# ST-Link-V2_1.net
KiCad netlist of a schematic drawn in Altium Designer
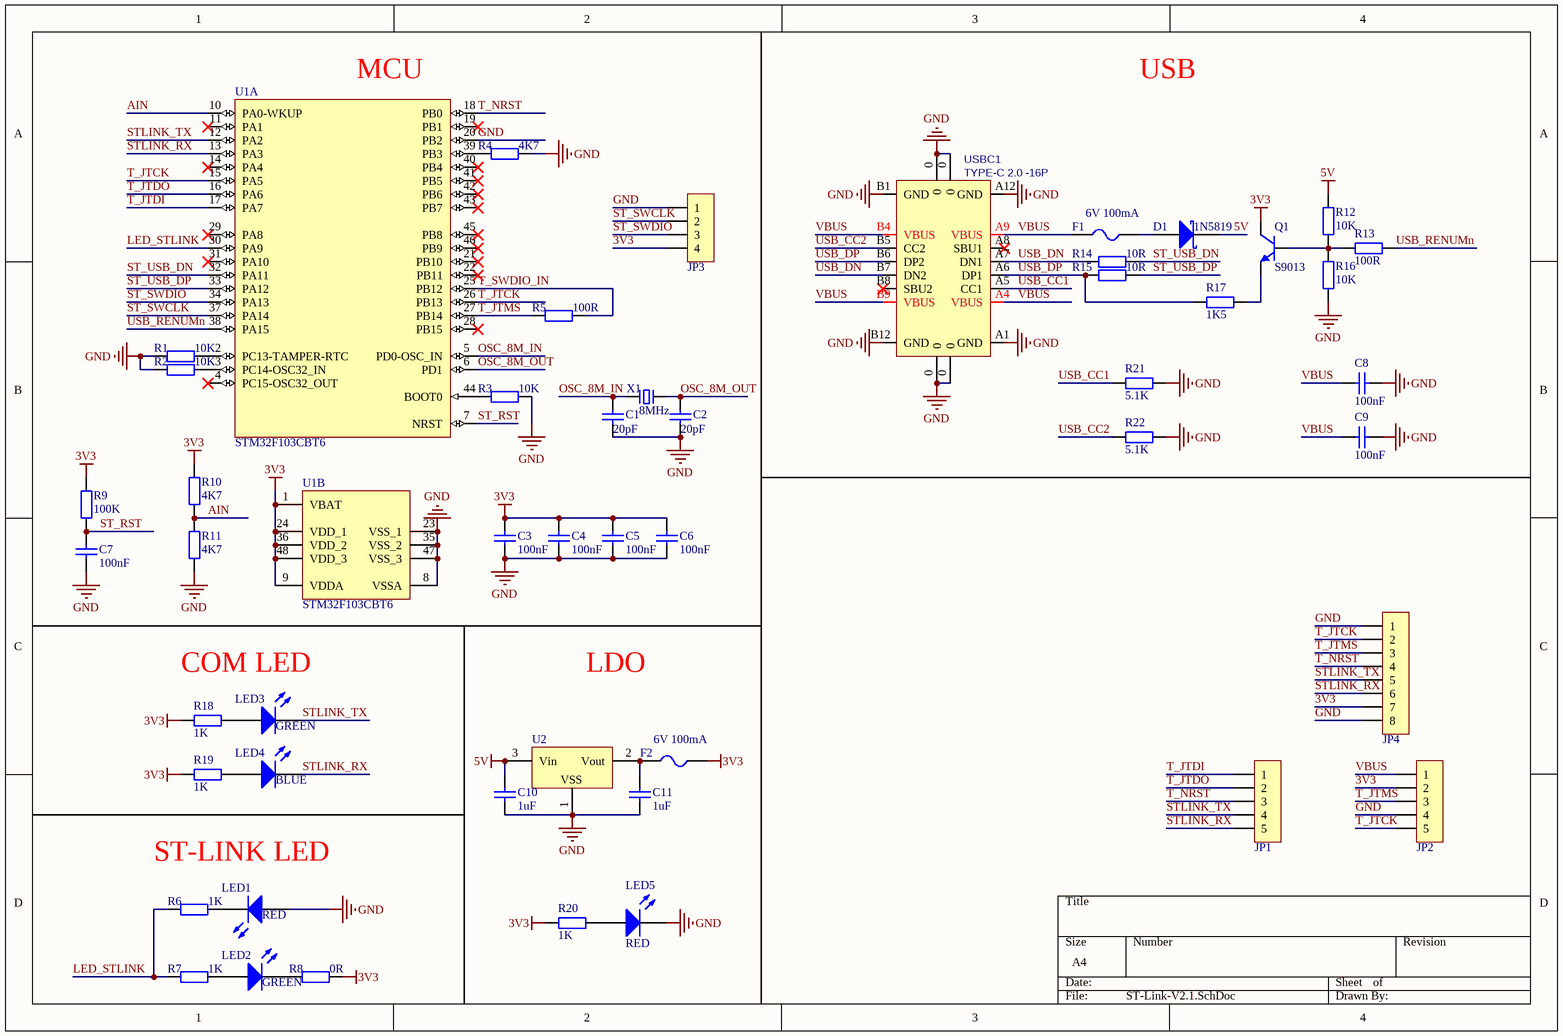
[diagram p0: ST-Link-V2.1.SchDoc]

(export (version "E")
  (design (tool "Eeschema 10.0.6"))
  (components
    (comp (ref "C1")
      (value "20pF")
      (footprint "C0402_M")
      (description "贴片电容/MLCC电容")
      (libsource (lib "0.1 - 电阻-电容-电感-保险丝-晶振-晶体-磁珠-电位器-法拉电容-馈通电容") (part "C"))
    )
    (comp (ref "C2")
      (value "20pF")
      (footprint "C0402_M")
      (description "贴片电容/MLCC电容")
      (libsource (lib "0.1 - 电阻-电容-电感-保险丝-晶振-晶体-磁珠-电位器-法拉电容-馈通电容") (part "C"))
    )
    (comp (ref "C3")
      (value "100nF")
      (footprint "C0402_M")
      (description "贴片电容/MLCC电容")
      (libsource (lib "0.1 - 电阻-电容-电感-保险丝-晶振-晶体-磁珠-电位器-法拉电容-馈通电容") (part "C"))
    )
    (comp (ref "C4")
      (value "100nF")
      (footprint "C0402_M")
      (description "贴片电容/MLCC电容")
      (libsource (lib "0.1 - 电阻-电容-电感-保险丝-晶振-晶体-磁珠-电位器-法拉电容-馈通电容") (part "C"))
    )
    (comp (ref "C5")
      (value "100nF")
      (footprint "C0402_M")
      (description "贴片电容/MLCC电容")
      (libsource (lib "0.1 - 电阻-电容-电感-保险丝-晶振-晶体-磁珠-电位器-法拉电容-馈通电容") (part "C"))
    )
    (comp (ref "C6")
      (value "100nF")
      (footprint "C0402_M")
      (description "贴片电容/MLCC电容")
      (libsource (lib "0.1 - 电阻-电容-电感-保险丝-晶振-晶体-磁珠-电位器-法拉电容-馈通电容") (part "C"))
    )
    (comp (ref "C7")
      (value "100nF")
      (footprint "C0402_M")
      (description "贴片电容/MLCC电容")
      (libsource (lib "0.1 - 电阻-电容-电感-保险丝-晶振-晶体-磁珠-电位器-法拉电容-馈通电容") (part "C"))
    )
    (comp (ref "C8")
      (value "100nF")
      (footprint "C0402_M")
      (description "贴片电容/MLCC电容")
      (libsource (lib "0.1 - 电阻-电容-电感-保险丝-晶振-晶体-磁珠-电位器-法拉电容-馈通电容") (part "C"))
    )
    (comp (ref "C9")
      (value "100nF")
      (footprint "C0402_M")
      (description "贴片电容/MLCC电容")
      (libsource (lib "0.1 - 电阻-电容-电感-保险丝-晶振-晶体-磁珠-电位器-法拉电容-馈通电容") (part "C"))
    )
    (comp (ref "C10")
      (value "1uF")
      (footprint "C0402_M")
      (description "贴片电容/MLCC电容")
      (libsource (lib "0.1 - 电阻-电容-电感-保险丝-晶振-晶体-磁珠-电位器-法拉电容-馈通电容") (part "C"))
    )
    (comp (ref "C11")
      (value "1uF")
      (footprint "C0402_M")
      (description "贴片电容/MLCC电容")
      (libsource (lib "0.1 - 电阻-电容-电感-保险丝-晶振-晶体-磁珠-电位器-法拉电容-馈通电容") (part "C"))
    )
    (comp (ref "D1")
      (value "1N5819")
      (footprint "SOD-323")
      (description "肖特基二极管")
      (libsource (lib "0.2 - 二极管-TVS-ESD-整流桥-放电管") (part "1N5819"))
    )
    (comp (ref "F1")
      (value "6V 100mA")
      (footprint "F0805")
      (description "方形保险丝")
      (libsource (lib "0.1 - 电阻-电容-电感-保险丝-晶振-晶体-磁珠-电位器-法拉电容-馈通电容") (part "FUSE-8.5*4.0*8.0"))
    )
    (comp (ref "F2")
      (value "6V 100mA")
      (footprint "F0805")
      (description "方形保险丝")
      (libsource (lib "0.1 - 电阻-电容-电感-保险丝-晶振-晶体-磁珠-电位器-法拉电容-馈通电容") (part "FUSE-8.5*4.0*8.0"))
    )
    (comp (ref "JP1")
      (value "HDR-1X5")
      (footprint "HDR2.54-WS-5P")
      (description "5P接插件")
      (libsource (lib "5.5 - 2.54mm连接器(KF2EDGK_XH2.54_2.54排针排母)") (part "Header 5"))
    )
    (comp (ref "JP2")
      (value "HDR-1X5")
      (footprint "HDR2.54-WS-5P")
      (description "5P接插件")
      (libsource (lib "5.5 - 2.54mm连接器(KF2EDGK_XH2.54_2.54排针排母)") (part "Header 5"))
    )
    (comp (ref "JP3")
      (value "HDR-1X4")
      (footprint "HDR1.27-LI-4P")
      (description "4P接插件")
      (libsource (lib "5.5 - 2.54mm连接器(KF2EDGK_XH2.54_2.54排针排母)") (part "Header 4"))
    )
    (comp (ref "JP4")
      (value "CON-8P")
      (footprint "FPC0.5-WT-8P-双侧触点")
      (description "8P连接器")
      (libsource (lib "4.9 - 0.5mm连接器(FPC0.5)") (part "Header 8"))
    )
    (comp (ref "LED1")
      (value "RED")
      (footprint "LED0402_R")
      (description "贴片LED")
      (libsource (lib "0.3 - LED发光二极管-IR二极管_接收管-光耦") (part "LED"))
    )
    (comp (ref "LED2")
      (value "GREEN")
      (footprint "LED0402_G")
      (description "贴片LED")
      (libsource (lib "0.3 - LED发光二极管-IR二极管_接收管-光耦") (part "LED"))
    )
    (comp (ref "LED3")
      (value "GREEN")
      (footprint "LED0402_G")
      (description "贴片LED")
      (libsource (lib "0.3 - LED发光二极管-IR二极管_接收管-光耦") (part "LED"))
    )
    (comp (ref "LED4")
      (value "BLUE")
      (footprint "LED0402_B")
      (description "贴片LED")
      (libsource (lib "0.3 - LED发光二极管-IR二极管_接收管-光耦") (part "LED"))
    )
    (comp (ref "LED5")
      (value "RED")
      (footprint "LED0402_R")
      (description "贴片LED")
      (libsource (lib "0.3 - LED发光二极管-IR二极管_接收管-光耦") (part "LED"))
    )
    (comp (ref "Q1")
      (value "S9013")
      (footprint "SOT23-3M")
      (description "低频放大-NPN型")
      (libsource (lib "0.4 - 三极管-场效应管-可控硅") (part "9013-DIP"))
    )
    (comp (ref "R1")
      (value "10K")
      (footprint "R0402_M")
      (description "贴片电阻")
      (libsource (lib "0.1 - 电阻-电容-电感-保险丝-晶振-晶体-磁珠-电位器-法拉电容-馈通电容") (part "R"))
    )
    (comp (ref "R2")
      (value "10K")
      (footprint "R0402_M")
      (description "贴片电阻")
      (libsource (lib "0.1 - 电阻-电容-电感-保险丝-晶振-晶体-磁珠-电位器-法拉电容-馈通电容") (part "R"))
    )
    (comp (ref "R3")
      (value "10K")
      (footprint "R0402_M")
      (description "贴片电阻")
      (libsource (lib "0.1 - 电阻-电容-电感-保险丝-晶振-晶体-磁珠-电位器-法拉电容-馈通电容") (part "R"))
    )
    (comp (ref "R4")
      (value "4K7")
      (footprint "R0402_M")
      (description "贴片电阻")
      (libsource (lib "0.1 - 电阻-电容-电感-保险丝-晶振-晶体-磁珠-电位器-法拉电容-馈通电容") (part "R"))
    )
    (comp (ref "R5")
      (value "100R")
      (footprint "R0402_M")
      (description "贴片电阻")
      (libsource (lib "0.1 - 电阻-电容-电感-保险丝-晶振-晶体-磁珠-电位器-法拉电容-馈通电容") (part "R"))
    )
    (comp (ref "R6")
      (value "1K")
      (footprint "R0402_M")
      (description "贴片电阻")
      (libsource (lib "0.1 - 电阻-电容-电感-保险丝-晶振-晶体-磁珠-电位器-法拉电容-馈通电容") (part "R"))
    )
    (comp (ref "R7")
      (value "1K")
      (footprint "R0402_M")
      (description "贴片电阻")
      (libsource (lib "0.1 - 电阻-电容-电感-保险丝-晶振-晶体-磁珠-电位器-法拉电容-馈通电容") (part "R"))
    )
    (comp (ref "R8")
      (value "0R")
      (footprint "R0402_M")
      (description "贴片电阻")
      (libsource (lib "0.1 - 电阻-电容-电感-保险丝-晶振-晶体-磁珠-电位器-法拉电容-馈通电容") (part "R"))
    )
    (comp (ref "R9")
      (value "100K")
      (footprint "R0402_M")
      (description "贴片电阻")
      (libsource (lib "0.1 - 电阻-电容-电感-保险丝-晶振-晶体-磁珠-电位器-法拉电容-馈通电容") (part "R"))
    )
    (comp (ref "R10")
      (value "4K7")
      (footprint "R0402_M")
      (description "贴片电阻")
      (libsource (lib "0.1 - 电阻-电容-电感-保险丝-晶振-晶体-磁珠-电位器-法拉电容-馈通电容") (part "R"))
    )
    (comp (ref "R11")
      (value "4K7")
      (footprint "R0402_M")
      (description "贴片电阻")
      (libsource (lib "0.1 - 电阻-电容-电感-保险丝-晶振-晶体-磁珠-电位器-法拉电容-馈通电容") (part "R"))
    )
    (comp (ref "R12")
      (value "10K")
      (footprint "R0402_M")
      (description "贴片电阻")
      (libsource (lib "0.1 - 电阻-电容-电感-保险丝-晶振-晶体-磁珠-电位器-法拉电容-馈通电容") (part "R"))
    )
    (comp (ref "R13")
      (value "100R")
      (footprint "R0402_M")
      (description "贴片电阻")
      (libsource (lib "0.1 - 电阻-电容-电感-保险丝-晶振-晶体-磁珠-电位器-法拉电容-馈通电容") (part "R"))
    )
    (comp (ref "R14")
      (value "10R")
      (footprint "R0402_M")
      (description "贴片电阻")
      (libsource (lib "0.1 - 电阻-电容-电感-保险丝-晶振-晶体-磁珠-电位器-法拉电容-馈通电容") (part "R"))
    )
    (comp (ref "R15")
      (value "10R")
      (footprint "R0402_M")
      (description "贴片电阻")
      (libsource (lib "0.1 - 电阻-电容-电感-保险丝-晶振-晶体-磁珠-电位器-法拉电容-馈通电容") (part "R"))
    )
    (comp (ref "R16")
      (value "10K")
      (footprint "R0402_M")
      (description "贴片电阻")
      (libsource (lib "0.1 - 电阻-电容-电感-保险丝-晶振-晶体-磁珠-电位器-法拉电容-馈通电容") (part "R"))
    )
    (comp (ref "R17")
      (value "1K5")
      (footprint "R0402_M")
      (description "贴片电阻")
      (libsource (lib "0.1 - 电阻-电容-电感-保险丝-晶振-晶体-磁珠-电位器-法拉电容-馈通电容") (part "R"))
    )
    (comp (ref "R18")
      (value "1K")
      (footprint "R0402_M")
      (description "贴片电阻")
      (libsource (lib "0.1 - 电阻-电容-电感-保险丝-晶振-晶体-磁珠-电位器-法拉电容-馈通电容") (part "R"))
    )
    (comp (ref "R19")
      (value "1K")
      (footprint "R0402_M")
      (description "贴片电阻")
      (libsource (lib "0.1 - 电阻-电容-电感-保险丝-晶振-晶体-磁珠-电位器-法拉电容-馈通电容") (part "R"))
    )
    (comp (ref "R20")
      (value "1K")
      (footprint "R0402_M")
      (description "贴片电阻")
      (libsource (lib "0.1 - 电阻-电容-电感-保险丝-晶振-晶体-磁珠-电位器-法拉电容-馈通电容") (part "R"))
    )
    (comp (ref "R21")
      (value "5.1K")
      (footprint "R0402_M")
      (description "贴片电阻")
      (libsource (lib "0.1 - 电阻-电容-电感-保险丝-晶振-晶体-磁珠-电位器-法拉电容-馈通电容") (part "R"))
    )
    (comp (ref "R22")
      (value "5.1K")
      (footprint "R0402_M")
      (description "贴片电阻")
      (libsource (lib "0.1 - 电阻-电容-电感-保险丝-晶振-晶体-磁珠-电位器-法拉电容-馈通电容") (part "R"))
    )
    (comp (ref "U1")
      (value "STM32F103CBT6")
      (footprint "STM-LQFP48_N")
      (libsource (lib "2.4 - STM32 F1系列单片机") (part "STM32F103CBT6"))
    )
    (comp (ref "U2")
      (value "XC6206P332MR")
      (footprint "SOT23-3N")
      (description "LDO 3.3V/0.25A")
      (libsource (lib "0.7 - 电源类芯片") (part "XC6206P332MR"))
    )
    (comp (ref "USBC1")
      (value "TYPE-C 2.0 -16P")
      (footprint "USB-C-SMD_16P")
      (description "USB2.0_Type-C_16Pin母座")
      (libsource (lib "0.6 - 电源_音频_USB Type-C_HDMI_XT60_5557_D-SUB_RJ45_SD-TF_SIM插座") (part "USB2.0_Type-C_16Pin"))
    )
    (comp (ref "X1")
      (value "8MHz")
      (footprint "OSC-5032-2P")
      (description "2脚无源晶振(谐振器）")
      (libsource (lib "0.1 - 电阻-电容-电感-保险丝-晶振-晶体-磁珠-电位器-法拉电容-馈通电容") (part "XTAL-2P"))
    )
  )
  (nets
    (net (code "1") (name "/AIN") (class "Default")
      (node (ref "R10") (pin "1") (pinfunction "1_1") (pintype "passive"))
      (node (ref "R11") (pin "2") (pinfunction "2_2") (pintype "passive"))
      (node (ref "U1") (pin "10") (pinfunction "PA0-WKUP_10") (pintype "bidirectional"))
    )
    (net (code "2") (name "/LED_STLINK") (class "Default")
      (node (ref "R6") (pin "1") (pinfunction "1_1") (pintype "passive"))
      (node (ref "R7") (pin "1") (pinfunction "1_1") (pintype "passive"))
      (node (ref "U1") (pin "30") (pinfunction "PA9_30") (pintype "bidirectional"))
    )
    (net (code "3") (name "/OSC_8M_IN") (class "Default")
      (node (ref "C1") (pin "2") (pinfunction "2_2") (pintype "passive"))
      (node (ref "U1") (pin "5") (pinfunction "PD0-OSC_IN_5") (pintype "bidirectional"))
      (node (ref "X1") (pin "1") (pinfunction "1_1") (pintype "passive"))
    )
    (net (code "4") (name "/OSC_8M_OUT") (class "Default")
      (node (ref "C2") (pin "2") (pinfunction "2_2") (pintype "passive"))
      (node (ref "U1") (pin "6") (pinfunction "PD1_6") (pintype "bidirectional"))
      (node (ref "X1") (pin "2") (pinfunction "2_2") (pintype "passive"))
    )
    (net (code "5") (name "/STLINK_RX") (class "Default")
      (node (ref "JP1") (pin "5") (pinfunction "5_5") (pintype "passive"))
      (node (ref "JP4") (pin "6") (pinfunction "6_6") (pintype "passive"))
      (node (ref "LED4") (pin "2") (pinfunction "K_2") (pintype "passive"))
      (node (ref "U1") (pin "13") (pinfunction "PA3_13") (pintype "bidirectional"))
    )
    (net (code "6") (name "/STLINK_TX") (class "Default")
      (node (ref "JP1") (pin "4") (pinfunction "4_4") (pintype "passive"))
      (node (ref "JP4") (pin "5") (pinfunction "5_5") (pintype "passive"))
      (node (ref "LED3") (pin "2") (pinfunction "K_2") (pintype "passive"))
      (node (ref "U1") (pin "12") (pinfunction "PA2_12") (pintype "bidirectional"))
    )
    (net (code "7") (name "/ST_RST") (class "Default")
      (node (ref "C7") (pin "2") (pinfunction "2_2") (pintype "passive"))
      (node (ref "R9") (pin "1") (pinfunction "1_1") (pintype "passive"))
      (node (ref "U1") (pin "7") (pinfunction "NRST_7") (pintype "bidirectional"))
    )
    (net (code "8") (name "/ST_SWCLK") (class "Default")
      (node (ref "JP3") (pin "2") (pinfunction "2_2") (pintype "passive"))
      (node (ref "U1") (pin "37") (pinfunction "PA14_37") (pintype "bidirectional"))
    )
    (net (code "9") (name "/ST_SWDIO") (class "Default")
      (node (ref "JP3") (pin "3") (pinfunction "3_3") (pintype "passive"))
      (node (ref "U1") (pin "34") (pinfunction "PA13_34") (pintype "bidirectional"))
    )
    (net (code "10") (name "/ST_USB_DN") (class "Default")
      (node (ref "R14") (pin "2") (pinfunction "2_2") (pintype "passive"))
      (node (ref "U1") (pin "32") (pinfunction "PA11_32") (pintype "bidirectional"))
    )
    (net (code "11") (name "/ST_USB_DP") (class "Default")
      (node (ref "R15") (pin "2") (pinfunction "2_2") (pintype "passive"))
      (node (ref "U1") (pin "33") (pinfunction "PA12_33") (pintype "bidirectional"))
    )
    (net (code "12") (name "/T_JTCK") (class "Default")
      (node (ref "JP2") (pin "5") (pinfunction "5_5") (pintype "passive"))
      (node (ref "JP4") (pin "2") (pinfunction "2_2") (pintype "passive"))
      (node (ref "U1") (pin "15") (pinfunction "PA5_15") (pintype "bidirectional"))
      (node (ref "U1") (pin "26") (pinfunction "PB13_26") (pintype "bidirectional"))
    )
    (net (code "13") (name "/T_JTDI") (class "Default")
      (node (ref "JP1") (pin "1") (pinfunction "1_1") (pintype "passive"))
      (node (ref "U1") (pin "17") (pinfunction "PA7_17") (pintype "bidirectional"))
    )
    (net (code "14") (name "/T_JTDO") (class "Default")
      (node (ref "JP1") (pin "2") (pinfunction "2_2") (pintype "passive"))
      (node (ref "U1") (pin "16") (pinfunction "PA6_16") (pintype "bidirectional"))
    )
    (net (code "15") (name "/T_JTMS") (class "Default")
      (node (ref "JP2") (pin "3") (pinfunction "3_3") (pintype "passive"))
      (node (ref "JP4") (pin "3") (pinfunction "3_3") (pintype "passive"))
      (node (ref "R5") (pin "1") (pinfunction "1_1") (pintype "passive"))
      (node (ref "U1") (pin "27") (pinfunction "PB14_27") (pintype "bidirectional"))
    )
    (net (code "16") (name "/T_NRST") (class "Default")
      (node (ref "JP1") (pin "3") (pinfunction "3_3") (pintype "passive"))
      (node (ref "JP4") (pin "4") (pinfunction "4_4") (pintype "passive"))
      (node (ref "U1") (pin "18") (pinfunction "PB0_18") (pintype "bidirectional"))
    )
    (net (code "17") (name "/T_SWDIO_IN") (class "Default")
      (node (ref "R5") (pin "2") (pinfunction "2_2") (pintype "passive"))
      (node (ref "U1") (pin "25") (pinfunction "PB12_25") (pintype "bidirectional"))
    )
    (net (code "18") (name "/USB_CC1") (class "Default")
      (node (ref "R21") (pin "2") (pinfunction "2_2") (pintype "passive"))
      (node (ref "USBC1") (pin "A5") (pinfunction "CC1_A5") (pintype "passive"))
    )
    (net (code "19") (name "/USB_CC2") (class "Default")
      (node (ref "R22") (pin "2") (pinfunction "2_2") (pintype "passive"))
      (node (ref "USBC1") (pin "B5") (pinfunction "CC2_B5") (pintype "passive"))
    )
    (net (code "20") (name "/USB_DN") (class "Default")
      (node (ref "R14") (pin "1") (pinfunction "1_1") (pintype "passive"))
      (node (ref "USBC1") (pin "A7") (pinfunction "DN1_A7") (pintype "passive"))
      (node (ref "USBC1") (pin "B7") (pinfunction "DN2_B7") (pintype "passive"))
    )
    (net (code "21") (name "/USB_DP") (class "Default")
      (node (ref "R15") (pin "1") (pinfunction "1_1") (pintype "passive"))
      (node (ref "R17") (pin "1") (pinfunction "1_1") (pintype "passive"))
      (node (ref "USBC1") (pin "A6") (pinfunction "DP1_A6") (pintype "passive"))
      (node (ref "USBC1") (pin "B6") (pinfunction "DP2_B6") (pintype "passive"))
    )
    (net (code "22") (name "/USB_RENUMn") (class "Default")
      (node (ref "R13") (pin "1") (pinfunction "1_1") (pintype "passive"))
      (node (ref "U1") (pin "38") (pinfunction "PA15_38") (pintype "bidirectional"))
    )
    (net (code "23") (name "/VBUS") (class "Default")
      (node (ref "C8") (pin "1") (pinfunction "1_1") (pintype "passive"))
      (node (ref "C9") (pin "1") (pinfunction "1_1") (pintype "passive"))
      (node (ref "F1") (pin "2") (pinfunction "2_2") (pintype "passive"))
      (node (ref "JP2") (pin "1") (pinfunction "1_1") (pintype "passive"))
      (node (ref "USBC1") (pin "A4") (pinfunction "VBUS_A4") (pintype "passive"))
      (node (ref "USBC1") (pin "A9") (pinfunction "VBUS_A9") (pintype "passive"))
      (node (ref "USBC1") (pin "B4") (pinfunction "VBUS_B4") (pintype "passive"))
      (node (ref "USBC1") (pin "B9") (pinfunction "VBUS_B9") (pintype "passive"))
    )
    (net (code "24") (name "3V3") (class "Default")
      (node (ref "C3") (pin "2") (pinfunction "2_2") (pintype "passive"))
      (node (ref "C4") (pin "2") (pinfunction "2_2") (pintype "passive"))
      (node (ref "C5") (pin "2") (pinfunction "2_2") (pintype "passive"))
      (node (ref "C6") (pin "2") (pinfunction "2_2") (pintype "passive"))
      (node (ref "F2") (pin "1") (pinfunction "1_1") (pintype "passive"))
      (node (ref "JP2") (pin "2") (pinfunction "2_2") (pintype "passive"))
      (node (ref "JP3") (pin "4") (pinfunction "4_4") (pintype "passive"))
      (node (ref "JP4") (pin "7") (pinfunction "7_7") (pintype "passive"))
      (node (ref "Q1") (pin "3") (pinfunction "C_3") (pintype "passive"))
      (node (ref "R10") (pin "2") (pinfunction "2_2") (pintype "passive"))
      (node (ref "R18") (pin "2") (pinfunction "2_2") (pintype "passive"))
      (node (ref "R19") (pin "2") (pinfunction "2_2") (pintype "passive"))
      (node (ref "R20") (pin "2") (pinfunction "2_2") (pintype "passive"))
      (node (ref "R8") (pin "2") (pinfunction "2_2") (pintype "passive"))
      (node (ref "R9") (pin "2") (pinfunction "2_2") (pintype "passive"))
      (node (ref "U1") (pin "1") (pinfunction "VBAT_1") (pintype "power_in"))
      (node (ref "U1") (pin "24") (pinfunction "VDD_1_24") (pintype "power_in"))
      (node (ref "U1") (pin "36") (pinfunction "VDD_2_36") (pintype "power_in"))
      (node (ref "U1") (pin "48") (pinfunction "VDD_3_48") (pintype "power_in"))
      (node (ref "U1") (pin "9") (pinfunction "VDDA_9") (pintype "power_in"))
    )
    (net (code "25") (name "5V") (class "Default")
      (node (ref "C10") (pin "2") (pinfunction "2_2") (pintype "passive"))
      (node (ref "D1") (pin "2") (pinfunction "K_2") (pintype "passive"))
      (node (ref "R12") (pin "2") (pinfunction "2_2") (pintype "passive"))
      (node (ref "U2") (pin "3") (pinfunction "Vin_3") (pintype "passive"))
    )
    (net (code "26") (name "GND") (class "Default")
      (node (ref "C1") (pin "1") (pinfunction "1_1") (pintype "passive"))
      (node (ref "C10") (pin "1") (pinfunction "1_1") (pintype "passive"))
      (node (ref "C11") (pin "1") (pinfunction "1_1") (pintype "passive"))
      (node (ref "C2") (pin "1") (pinfunction "1_1") (pintype "passive"))
      (node (ref "C3") (pin "1") (pinfunction "1_1") (pintype "passive"))
      (node (ref "C4") (pin "1") (pinfunction "1_1") (pintype "passive"))
      (node (ref "C5") (pin "1") (pinfunction "1_1") (pintype "passive"))
      (node (ref "C6") (pin "1") (pinfunction "1_1") (pintype "passive"))
      (node (ref "C7") (pin "1") (pinfunction "1_1") (pintype "passive"))
      (node (ref "C8") (pin "2") (pinfunction "2_2") (pintype "passive"))
      (node (ref "C9") (pin "2") (pinfunction "2_2") (pintype "passive"))
      (node (ref "JP2") (pin "4") (pinfunction "4_4") (pintype "passive"))
      (node (ref "JP3") (pin "1") (pinfunction "1_1") (pintype "passive"))
      (node (ref "JP4") (pin "1") (pinfunction "1_1") (pintype "passive"))
      (node (ref "JP4") (pin "8") (pinfunction "8_8") (pintype "passive"))
      (node (ref "LED1") (pin "1") (pinfunction "A_1") (pintype "passive"))
      (node (ref "LED5") (pin "2") (pinfunction "K_2") (pintype "passive"))
      (node (ref "R1") (pin "1") (pinfunction "1_1") (pintype "passive"))
      (node (ref "R11") (pin "1") (pinfunction "1_1") (pintype "passive"))
      (node (ref "R16") (pin "1") (pinfunction "1_1") (pintype "passive"))
      (node (ref "R2") (pin "1") (pinfunction "1_1") (pintype "passive"))
      (node (ref "R21") (pin "1") (pinfunction "1_1") (pintype "passive"))
      (node (ref "R22") (pin "1") (pinfunction "1_1") (pintype "passive"))
      (node (ref "R3") (pin "2") (pinfunction "2_2") (pintype "passive"))
      (node (ref "R4") (pin "2") (pinfunction "2_2") (pintype "passive"))
      (node (ref "U1") (pin "20") (pinfunction "PB2_20") (pintype "bidirectional"))
      (node (ref "U1") (pin "23") (pinfunction "VSS_1_23") (pintype "power_in"))
      (node (ref "U1") (pin "35") (pinfunction "VSS_2_35") (pintype "power_in"))
      (node (ref "U1") (pin "47") (pinfunction "VSS_3_47") (pintype "power_in"))
      (node (ref "U1") (pin "8") (pinfunction "VSSA_8") (pintype "power_in"))
      (node (ref "U2") (pin "1") (pinfunction "GND_1") (pintype "passive"))
      (node (ref "USBC1") (pin "0") (pinfunction "0_0") (pintype "passive"))
      (node (ref "USBC1") (pin "A1") (pinfunction "GND_A1") (pintype "passive"))
      (node (ref "USBC1") (pin "A12") (pinfunction "GND_A12") (pintype "passive"))
      (node (ref "USBC1") (pin "B1") (pinfunction "GND_B1") (pintype "passive"))
      (node (ref "USBC1") (pin "B12") (pinfunction "GND_B12") (pintype "passive"))
    )
    (net (code "27") (name "Net-(D1-A)") (class "Default")
      (node (ref "D1") (pin "1") (pinfunction "A_1") (pintype "passive"))
      (node (ref "F1") (pin "1") (pinfunction "1_1") (pintype "passive"))
    )
    (net (code "28") (name "Net-(LED1-K)") (class "Default")
      (node (ref "LED1") (pin "2") (pinfunction "K_2") (pintype "passive"))
      (node (ref "R6") (pin "2") (pinfunction "2_2") (pintype "passive"))
    )
    (net (code "29") (name "Net-(LED2-A)") (class "Default")
      (node (ref "LED2") (pin "1") (pinfunction "A_1") (pintype "passive"))
      (node (ref "R7") (pin "2") (pinfunction "2_2") (pintype "passive"))
    )
    (net (code "30") (name "Net-(LED2-K)") (class "Default")
      (node (ref "LED2") (pin "2") (pinfunction "K_2") (pintype "passive"))
      (node (ref "R8") (pin "1") (pinfunction "1_1") (pintype "passive"))
    )
    (net (code "31") (name "Net-(LED3-A)") (class "Default")
      (node (ref "LED3") (pin "1") (pinfunction "A_1") (pintype "passive"))
      (node (ref "R18") (pin "1") (pinfunction "1_1") (pintype "passive"))
    )
    (net (code "32") (name "Net-(LED4-A)") (class "Default")
      (node (ref "LED4") (pin "1") (pinfunction "A_1") (pintype "passive"))
      (node (ref "R19") (pin "1") (pinfunction "1_1") (pintype "passive"))
    )
    (net (code "33") (name "Net-(LED5-A)") (class "Default")
      (node (ref "LED5") (pin "1") (pinfunction "A_1") (pintype "passive"))
      (node (ref "R20") (pin "1") (pinfunction "1_1") (pintype "passive"))
    )
    (net (code "34") (name "Net-(Q1-B)") (class "Default")
      (node (ref "Q1") (pin "2") (pinfunction "B_2") (pintype "passive"))
      (node (ref "R12") (pin "1") (pinfunction "1_1") (pintype "passive"))
      (node (ref "R13") (pin "2") (pinfunction "2_2") (pintype "passive"))
      (node (ref "R16") (pin "2") (pinfunction "2_2") (pintype "passive"))
    )
    (net (code "35") (name "Net-(Q1-E)") (class "Default")
      (node (ref "Q1") (pin "1") (pinfunction "E_1") (pintype "passive"))
      (node (ref "R17") (pin "2") (pinfunction "2_2") (pintype "passive"))
    )
    (net (code "36") (name "Net-(U1A-BOOT0)") (class "Default")
      (node (ref "R3") (pin "1") (pinfunction "1_1") (pintype "passive"))
      (node (ref "U1") (pin "44") (pinfunction "BOOT0_44") (pintype "input"))
    )
    (net (code "37") (name "Net-(U1A-PB3)") (class "Default")
      (node (ref "R4") (pin "1") (pinfunction "1_1") (pintype "passive"))
      (node (ref "U1") (pin "39") (pinfunction "PB3_39") (pintype "bidirectional"))
    )
    (net (code "38") (name "Net-(U1A-PC13-TAMPER-RTC)") (class "Default")
      (node (ref "R1") (pin "2") (pinfunction "2_2") (pintype "passive"))
      (node (ref "U1") (pin "2") (pinfunction "PC13-TAMPER-RTC_2") (pintype "bidirectional"))
    )
    (net (code "39") (name "Net-(U1A-PC14-OSC32_IN)") (class "Default")
      (node (ref "R2") (pin "2") (pinfunction "2_2") (pintype "passive"))
      (node (ref "U1") (pin "3") (pinfunction "PC14-OSC32_IN_3") (pintype "bidirectional"))
    )
    (net (code "40") (name "Net-(U2-Vout)") (class "Default")
      (node (ref "C11") (pin "2") (pinfunction "2_2") (pintype "passive"))
      (node (ref "F2") (pin "2") (pinfunction "2_2") (pintype "passive"))
      (node (ref "U2") (pin "2") (pinfunction "Vout_2") (pintype "passive"))
    )
    (net (code "41") (name "unconnected-(U1A-PA1-Pad11)") (class "Default")
      (node (ref "U1") (pin "11") (pinfunction "PA1_11") (pintype "bidirectional+no_connect"))
    )
    (net (code "42") (name "unconnected-(U1A-PA4-Pad14)") (class "Default")
      (node (ref "U1") (pin "14") (pinfunction "PA4_14") (pintype "bidirectional+no_connect"))
    )
    (net (code "43") (name "unconnected-(U1A-PA8-Pad29)") (class "Default")
      (node (ref "U1") (pin "29") (pinfunction "PA8_29") (pintype "bidirectional+no_connect"))
    )
    (net (code "44") (name "unconnected-(U1A-PA10-Pad31)") (class "Default")
      (node (ref "U1") (pin "31") (pinfunction "PA10_31") (pintype "bidirectional+no_connect"))
    )
    (net (code "45") (name "unconnected-(U1A-PB1-Pad19)") (class "Default")
      (node (ref "U1") (pin "19") (pinfunction "PB1_19") (pintype "bidirectional+no_connect"))
    )
    (net (code "46") (name "unconnected-(U1A-PB4-Pad40)") (class "Default")
      (node (ref "U1") (pin "40") (pinfunction "PB4_40") (pintype "bidirectional+no_connect"))
    )
    (net (code "47") (name "unconnected-(U1A-PB5-Pad41)") (class "Default")
      (node (ref "U1") (pin "41") (pinfunction "PB5_41") (pintype "bidirectional+no_connect"))
    )
    (net (code "48") (name "unconnected-(U1A-PB6-Pad42)") (class "Default")
      (node (ref "U1") (pin "42") (pinfunction "PB6_42") (pintype "bidirectional+no_connect"))
    )
    (net (code "49") (name "unconnected-(U1A-PB7-Pad43)") (class "Default")
      (node (ref "U1") (pin "43") (pinfunction "PB7_43") (pintype "bidirectional+no_connect"))
    )
    (net (code "50") (name "unconnected-(U1A-PB8-Pad45)") (class "Default")
      (node (ref "U1") (pin "45") (pinfunction "PB8_45") (pintype "bidirectional+no_connect"))
    )
    (net (code "51") (name "unconnected-(U1A-PB9-Pad46)") (class "Default")
      (node (ref "U1") (pin "46") (pinfunction "PB9_46") (pintype "bidirectional+no_connect"))
    )
    (net (code "52") (name "unconnected-(U1A-PB10-Pad21)") (class "Default")
      (node (ref "U1") (pin "21") (pinfunction "PB10_21") (pintype "bidirectional+no_connect"))
    )
    (net (code "53") (name "unconnected-(U1A-PB11-Pad22)") (class "Default")
      (node (ref "U1") (pin "22") (pinfunction "PB11_22") (pintype "bidirectional+no_connect"))
    )
    (net (code "54") (name "unconnected-(U1A-PB15-Pad28)") (class "Default")
      (node (ref "U1") (pin "28") (pinfunction "PB15_28") (pintype "bidirectional+no_connect"))
    )
    (net (code "55") (name "unconnected-(U1A-PC15-OSC32_OUT-Pad4)") (class "Default")
      (node (ref "U1") (pin "4") (pinfunction "PC15-OSC32_OUT_4") (pintype "bidirectional+no_connect"))
    )
    (net (code "56") (name "unconnected-(USBC1-SBU1-PadA8)") (class "Default")
      (node (ref "USBC1") (pin "A8") (pinfunction "SBU1_A8") (pintype "passive+no_connect"))
    )
    (net (code "57") (name "unconnected-(USBC1-SBU2-PadB8)") (class "Default")
      (node (ref "USBC1") (pin "B8") (pinfunction "SBU2_B8") (pintype "passive+no_connect"))
    )
  )
)
